# X002B.net
KiCad netlist of a schematic drawn in EAGLE
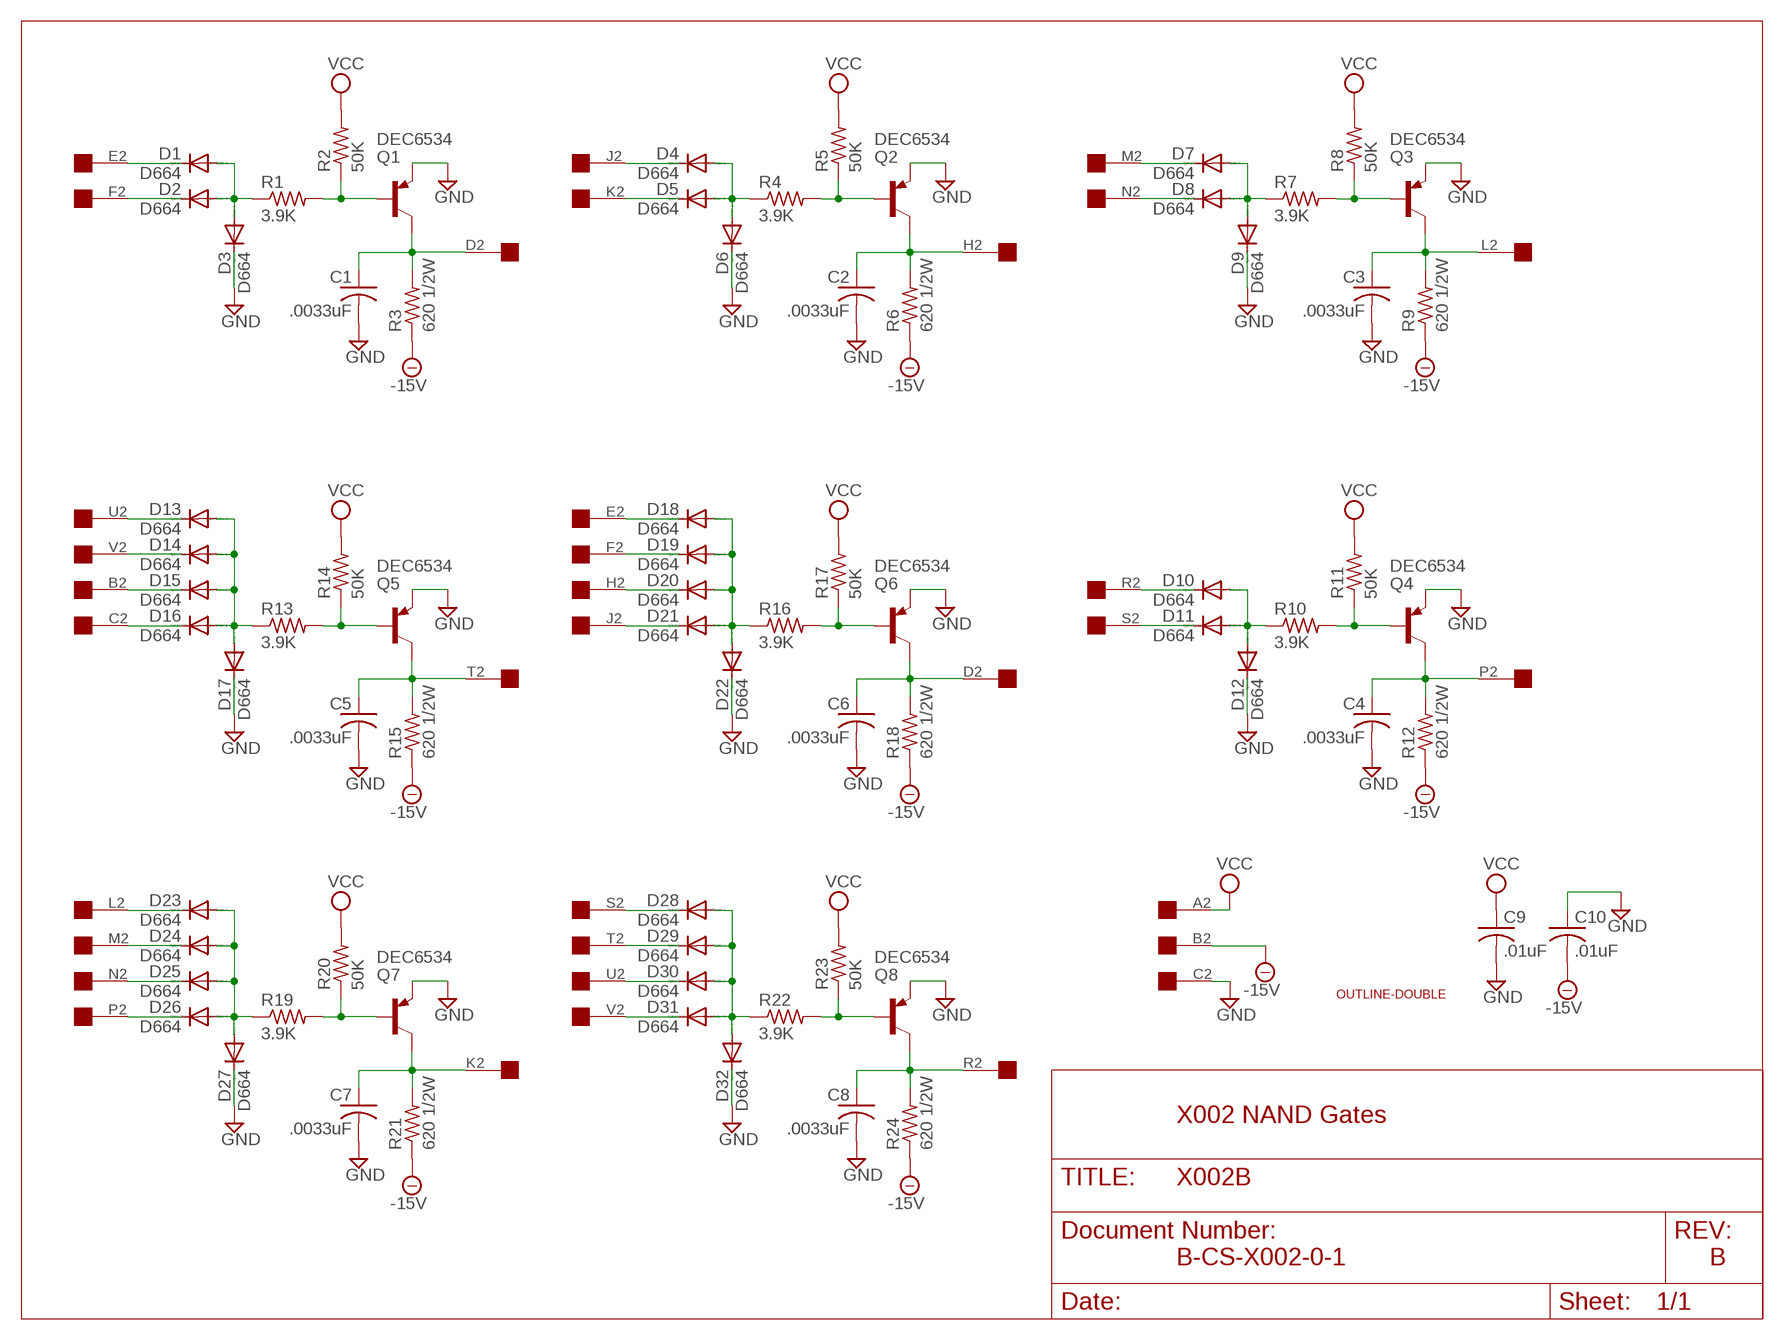
[diagram p0: schematic, sheet 1]

(export (version "E")
  (design (tool "Eeschema 10.0.6"))
  (components
    (comp (ref "A")
      (value "EDGE-1")
      (footprint "eagle-import:EDGE-CON1")
      (libsource (lib "eagle-import") (part "EDGE-1"))
    )
    (comp (ref "B")
      (value "EDGE-1")
      (footprint "eagle-import:EDGE-CON1")
      (libsource (lib "eagle-import") (part "EDGE-1"))
    )
    (comp (ref "C1")
      (value ".0033uF")
      (footprint "eagle-import:C225-062X268")
      (libsource (lib "eagle-import") (part "C-US225-062X268"))
    )
    (comp (ref "C2")
      (value ".0033uF")
      (footprint "eagle-import:C225-062X268")
      (libsource (lib "eagle-import") (part "C-US225-062X268"))
    )
    (comp (ref "C3")
      (value ".0033uF")
      (footprint "eagle-import:C225-062X268")
      (libsource (lib "eagle-import") (part "C-US225-062X268"))
    )
    (comp (ref "C4")
      (value ".0033uF")
      (footprint "eagle-import:C225-062X268")
      (libsource (lib "eagle-import") (part "C-US225-062X268"))
    )
    (comp (ref "C5")
      (value ".0033uF")
      (footprint "eagle-import:C225-062X268")
      (libsource (lib "eagle-import") (part "C-US225-062X268"))
    )
    (comp (ref "C6")
      (value ".0033uF")
      (footprint "eagle-import:C225-062X268")
      (libsource (lib "eagle-import") (part "C-US225-062X268"))
    )
    (comp (ref "C7")
      (value ".0033uF")
      (footprint "eagle-import:C225-062X268")
      (libsource (lib "eagle-import") (part "C-US225-062X268"))
    )
    (comp (ref "C8")
      (value ".0033uF")
      (footprint "eagle-import:C225-062X268")
      (libsource (lib "eagle-import") (part "C-US225-062X268"))
    )
    (comp (ref "C9")
      (value ".01uF")
      (footprint "eagle-import:C050-025X075")
      (libsource (lib "eagle-import") (part "C-US050-025X075"))
    )
    (comp (ref "C10")
      (value ".01uF")
      (footprint "eagle-import:C050-025X075")
      (libsource (lib "eagle-import") (part "C-US050-025X075"))
    )
    (comp (ref "D1")
      (value "D664")
      (footprint "eagle-import:DO35-10")
      (libsource (lib "eagle-import") (part "DIODE-DO35-10"))
    )
    (comp (ref "D2")
      (value "D664")
      (footprint "eagle-import:DO35-10")
      (libsource (lib "eagle-import") (part "DIODE-DO35-10"))
    )
    (comp (ref "D3")
      (value "D664")
      (footprint "eagle-import:DO35-10")
      (libsource (lib "eagle-import") (part "DIODE-DO35-10"))
    )
    (comp (ref "D4")
      (value "D664")
      (footprint "eagle-import:DO35-10")
      (libsource (lib "eagle-import") (part "DIODE-DO35-10"))
    )
    (comp (ref "D5")
      (value "D664")
      (footprint "eagle-import:DO35-10")
      (libsource (lib "eagle-import") (part "DIODE-DO35-10"))
    )
    (comp (ref "D6")
      (value "D664")
      (footprint "eagle-import:DO35-10")
      (libsource (lib "eagle-import") (part "DIODE-DO35-10"))
    )
    (comp (ref "D7")
      (value "D664")
      (footprint "eagle-import:DO35-10")
      (libsource (lib "eagle-import") (part "DIODE-DO35-10"))
    )
    (comp (ref "D8")
      (value "D664")
      (footprint "eagle-import:DO35-10")
      (libsource (lib "eagle-import") (part "DIODE-DO35-10"))
    )
    (comp (ref "D9")
      (value "D664")
      (footprint "eagle-import:DO35-10")
      (libsource (lib "eagle-import") (part "DIODE-DO35-10"))
    )
    (comp (ref "D10")
      (value "D664")
      (footprint "eagle-import:DO35-10")
      (libsource (lib "eagle-import") (part "DIODE-DO35-10"))
    )
    (comp (ref "D11")
      (value "D664")
      (footprint "eagle-import:DO35-10")
      (libsource (lib "eagle-import") (part "DIODE-DO35-10"))
    )
    (comp (ref "D12")
      (value "D664")
      (footprint "eagle-import:DO35-10")
      (libsource (lib "eagle-import") (part "DIODE-DO35-10"))
    )
    (comp (ref "D13")
      (value "D664")
      (footprint "eagle-import:DO35-10")
      (libsource (lib "eagle-import") (part "DIODE-DO35-10"))
    )
    (comp (ref "D14")
      (value "D664")
      (footprint "eagle-import:DO35-10")
      (libsource (lib "eagle-import") (part "DIODE-DO35-10"))
    )
    (comp (ref "D15")
      (value "D664")
      (footprint "eagle-import:DO35-10")
      (libsource (lib "eagle-import") (part "DIODE-DO35-10"))
    )
    (comp (ref "D16")
      (value "D664")
      (footprint "eagle-import:DO35-10")
      (libsource (lib "eagle-import") (part "DIODE-DO35-10"))
    )
    (comp (ref "D17")
      (value "D664")
      (footprint "eagle-import:DO35-10")
      (libsource (lib "eagle-import") (part "DIODE-DO35-10"))
    )
    (comp (ref "D18")
      (value "D664")
      (footprint "eagle-import:DO35-10")
      (libsource (lib "eagle-import") (part "DIODE-DO35-10"))
    )
    (comp (ref "D19")
      (value "D664")
      (footprint "eagle-import:DO35-10")
      (libsource (lib "eagle-import") (part "DIODE-DO35-10"))
    )
    (comp (ref "D20")
      (value "D664")
      (footprint "eagle-import:DO35-10")
      (libsource (lib "eagle-import") (part "DIODE-DO35-10"))
    )
    (comp (ref "D21")
      (value "D664")
      (footprint "eagle-import:DO35-10")
      (libsource (lib "eagle-import") (part "DIODE-DO35-10"))
    )
    (comp (ref "D22")
      (value "D664")
      (footprint "eagle-import:DO35-10")
      (libsource (lib "eagle-import") (part "DIODE-DO35-10"))
    )
    (comp (ref "D23")
      (value "D664")
      (footprint "eagle-import:DO35-10")
      (libsource (lib "eagle-import") (part "DIODE-DO35-10"))
    )
    (comp (ref "D24")
      (value "D664")
      (footprint "eagle-import:DO35-10")
      (libsource (lib "eagle-import") (part "DIODE-DO35-10"))
    )
    (comp (ref "D25")
      (value "D664")
      (footprint "eagle-import:DO35-10")
      (libsource (lib "eagle-import") (part "DIODE-DO35-10"))
    )
    (comp (ref "D26")
      (value "D664")
      (footprint "eagle-import:DO35-10")
      (libsource (lib "eagle-import") (part "DIODE-DO35-10"))
    )
    (comp (ref "D27")
      (value "D664")
      (footprint "eagle-import:DO35-10")
      (libsource (lib "eagle-import") (part "DIODE-DO35-10"))
    )
    (comp (ref "D28")
      (value "D664")
      (footprint "eagle-import:DO35-10")
      (libsource (lib "eagle-import") (part "DIODE-DO35-10"))
    )
    (comp (ref "D29")
      (value "D664")
      (footprint "eagle-import:DO35-10")
      (libsource (lib "eagle-import") (part "DIODE-DO35-10"))
    )
    (comp (ref "D30")
      (value "D664")
      (footprint "eagle-import:DO35-10")
      (libsource (lib "eagle-import") (part "DIODE-DO35-10"))
    )
    (comp (ref "D31")
      (value "D664")
      (footprint "eagle-import:DO35-10")
      (libsource (lib "eagle-import") (part "DIODE-DO35-10"))
    )
    (comp (ref "D32")
      (value "D664")
      (footprint "eagle-import:DO35-10")
      (libsource (lib "eagle-import") (part "DIODE-DO35-10"))
    )
    (comp (ref "Q1")
      (value "DEC6534")
      (footprint "eagle-import:TO5")
      (libsource (lib "eagle-import") (part "-PNP-TO5"))
    )
    (comp (ref "Q2")
      (value "DEC6534")
      (footprint "eagle-import:TO5")
      (libsource (lib "eagle-import") (part "-PNP-TO5"))
    )
    (comp (ref "Q3")
      (value "DEC6534")
      (footprint "eagle-import:TO5")
      (libsource (lib "eagle-import") (part "-PNP-TO5"))
    )
    (comp (ref "Q4")
      (value "DEC6534")
      (footprint "eagle-import:TO5")
      (libsource (lib "eagle-import") (part "-PNP-TO5"))
    )
    (comp (ref "Q5")
      (value "DEC6534")
      (footprint "eagle-import:TO5")
      (libsource (lib "eagle-import") (part "-PNP-TO5"))
    )
    (comp (ref "Q6")
      (value "DEC6534")
      (footprint "eagle-import:TO5")
      (libsource (lib "eagle-import") (part "-PNP-TO5"))
    )
    (comp (ref "Q7")
      (value "DEC6534")
      (footprint "eagle-import:TO5")
      (libsource (lib "eagle-import") (part "-PNP-TO5"))
    )
    (comp (ref "Q8")
      (value "DEC6534")
      (footprint "eagle-import:TO5")
      (libsource (lib "eagle-import") (part "-PNP-TO5"))
    )
    (comp (ref "R1")
      (value "3.9K")
      (footprint "eagle-import:0207_10")
      (libsource (lib "eagle-import") (part "R-US_0207/10"))
    )
    (comp (ref "R2")
      (value "50K")
      (footprint "eagle-import:0207_10")
      (libsource (lib "eagle-import") (part "R-US_0207/10"))
    )
    (comp (ref "R3")
      (value "620 1/2W")
      (footprint "eagle-import:0414_15")
      (libsource (lib "eagle-import") (part "R-US_0414/15"))
    )
    (comp (ref "R4")
      (value "3.9K")
      (footprint "eagle-import:0207_10")
      (libsource (lib "eagle-import") (part "R-US_0207/10"))
    )
    (comp (ref "R5")
      (value "50K")
      (footprint "eagle-import:0207_10")
      (libsource (lib "eagle-import") (part "R-US_0207/10"))
    )
    (comp (ref "R6")
      (value "620 1/2W")
      (footprint "eagle-import:0414_15")
      (libsource (lib "eagle-import") (part "R-US_0414/15"))
    )
    (comp (ref "R7")
      (value "3.9K")
      (footprint "eagle-import:0207_10")
      (libsource (lib "eagle-import") (part "R-US_0207/10"))
    )
    (comp (ref "R8")
      (value "50K")
      (footprint "eagle-import:0207_10")
      (libsource (lib "eagle-import") (part "R-US_0207/10"))
    )
    (comp (ref "R9")
      (value "620 1/2W")
      (footprint "eagle-import:0414_15")
      (libsource (lib "eagle-import") (part "R-US_0414/15"))
    )
    (comp (ref "R10")
      (value "3.9K")
      (footprint "eagle-import:0207_10")
      (libsource (lib "eagle-import") (part "R-US_0207/10"))
    )
    (comp (ref "R11")
      (value "50K")
      (footprint "eagle-import:0207_10")
      (libsource (lib "eagle-import") (part "R-US_0207/10"))
    )
    (comp (ref "R12")
      (value "620 1/2W")
      (footprint "eagle-import:0414_15")
      (libsource (lib "eagle-import") (part "R-US_0414/15"))
    )
    (comp (ref "R13")
      (value "3.9K")
      (footprint "eagle-import:0207_10")
      (libsource (lib "eagle-import") (part "R-US_0207/10"))
    )
    (comp (ref "R14")
      (value "50K")
      (footprint "eagle-import:0207_10")
      (libsource (lib "eagle-import") (part "R-US_0207/10"))
    )
    (comp (ref "R15")
      (value "620 1/2W")
      (footprint "eagle-import:0414_15")
      (libsource (lib "eagle-import") (part "R-US_0414/15"))
    )
    (comp (ref "R16")
      (value "3.9K")
      (footprint "eagle-import:0207_10")
      (libsource (lib "eagle-import") (part "R-US_0207/10"))
    )
    (comp (ref "R17")
      (value "50K")
      (footprint "eagle-import:0207_10")
      (libsource (lib "eagle-import") (part "R-US_0207/10"))
    )
    (comp (ref "R18")
      (value "620 1/2W")
      (footprint "eagle-import:0414_15")
      (libsource (lib "eagle-import") (part "R-US_0414/15"))
    )
    (comp (ref "R19")
      (value "3.9K")
      (footprint "eagle-import:0207_10")
      (libsource (lib "eagle-import") (part "R-US_0207/10"))
    )
    (comp (ref "R20")
      (value "50K")
      (footprint "eagle-import:0207_10")
      (libsource (lib "eagle-import") (part "R-US_0207/10"))
    )
    (comp (ref "R21")
      (value "620 1/2W")
      (footprint "eagle-import:0414_15")
      (libsource (lib "eagle-import") (part "R-US_0414/15"))
    )
    (comp (ref "R22")
      (value "3.9K")
      (footprint "eagle-import:0207_10")
      (libsource (lib "eagle-import") (part "R-US_0207/10"))
    )
    (comp (ref "R23")
      (value "50K")
      (footprint "eagle-import:0207_10")
      (libsource (lib "eagle-import") (part "R-US_0207/10"))
    )
    (comp (ref "R24")
      (value "620 1/2W")
      (footprint "eagle-import:0414_15")
      (libsource (lib "eagle-import") (part "R-US_0414/15"))
    )
    (comp (ref "U$1")
      (value "OUTLINE-DOUBLE")
      (footprint "eagle-import:DOUBLE")
      (libsource (lib "eagle-import") (part "OUTLINE-DOUBLE"))
    )
  )
  (nets
    (net (code "1") (name "-15V") (class "Default")
      (node (ref "A") (pin "B2") (pinfunction "1_B2") (pintype "bidirectional"))
      (node (ref "C10") (pin "2") (pinfunction "2_2") (pintype "passive"))
      (node (ref "R12") (pin "1") (pinfunction "1_1") (pintype "passive"))
      (node (ref "R15") (pin "1") (pinfunction "1_1") (pintype "passive"))
      (node (ref "R18") (pin "1") (pinfunction "1_1") (pintype "passive"))
      (node (ref "R21") (pin "1") (pinfunction "1_1") (pintype "passive"))
      (node (ref "R24") (pin "1") (pinfunction "1_1") (pintype "passive"))
      (node (ref "R3") (pin "1") (pinfunction "1_1") (pintype "passive"))
      (node (ref "R6") (pin "1") (pinfunction "1_1") (pintype "passive"))
      (node (ref "R9") (pin "1") (pinfunction "1_1") (pintype "passive"))
    )
    (net (code "2") (name "GND") (class "Default")
      (node (ref "A") (pin "C2") (pinfunction "1_C2") (pintype "bidirectional"))
      (node (ref "C1") (pin "2") (pinfunction "2_2") (pintype "passive"))
      (node (ref "C10") (pin "1") (pinfunction "1_1") (pintype "passive"))
      (node (ref "C2") (pin "2") (pinfunction "2_2") (pintype "passive"))
      (node (ref "C3") (pin "2") (pinfunction "2_2") (pintype "passive"))
      (node (ref "C4") (pin "2") (pinfunction "2_2") (pintype "passive"))
      (node (ref "C5") (pin "2") (pinfunction "2_2") (pintype "passive"))
      (node (ref "C6") (pin "2") (pinfunction "2_2") (pintype "passive"))
      (node (ref "C7") (pin "2") (pinfunction "2_2") (pintype "passive"))
      (node (ref "C8") (pin "2") (pinfunction "2_2") (pintype "passive"))
      (node (ref "C9") (pin "2") (pinfunction "2_2") (pintype "passive"))
      (node (ref "D12") (pin "C") (pinfunction "C_C") (pintype "passive"))
      (node (ref "D17") (pin "C") (pinfunction "C_C") (pintype "passive"))
      (node (ref "D22") (pin "C") (pinfunction "C_C") (pintype "passive"))
      (node (ref "D27") (pin "C") (pinfunction "C_C") (pintype "passive"))
      (node (ref "D3") (pin "C") (pinfunction "C_C") (pintype "passive"))
      (node (ref "D32") (pin "C") (pinfunction "C_C") (pintype "passive"))
      (node (ref "D6") (pin "C") (pinfunction "C_C") (pintype "passive"))
      (node (ref "D9") (pin "C") (pinfunction "C_C") (pintype "passive"))
      (node (ref "Q1") (pin "1") (pinfunction "E_1") (pintype "passive"))
      (node (ref "Q2") (pin "1") (pinfunction "E_1") (pintype "passive"))
      (node (ref "Q3") (pin "1") (pinfunction "E_1") (pintype "passive"))
      (node (ref "Q4") (pin "1") (pinfunction "E_1") (pintype "passive"))
      (node (ref "Q5") (pin "1") (pinfunction "E_1") (pintype "passive"))
      (node (ref "Q6") (pin "1") (pinfunction "E_1") (pintype "passive"))
      (node (ref "Q7") (pin "1") (pinfunction "E_1") (pintype "passive"))
      (node (ref "Q8") (pin "1") (pinfunction "E_1") (pintype "passive"))
    )
    (net (code "3") (name "Net-(AD-1)") (class "Default")
      (node (ref "A") (pin "D2") (pinfunction "1_D2") (pintype "bidirectional"))
      (node (ref "C1") (pin "1") (pinfunction "1_1") (pintype "passive"))
      (node (ref "Q1") (pin "3") (pinfunction "C_3") (pintype "passive"))
      (node (ref "R3") (pin "2") (pinfunction "2_2") (pintype "passive"))
    )
    (net (code "4") (name "Net-(AE-1)") (class "Default")
      (node (ref "A") (pin "E2") (pinfunction "1_E2") (pintype "bidirectional"))
      (node (ref "D1") (pin "C") (pinfunction "C_C") (pintype "passive"))
    )
    (net (code "5") (name "Net-(AF-1)") (class "Default")
      (node (ref "A") (pin "F2") (pinfunction "1_F2") (pintype "bidirectional"))
      (node (ref "D2") (pin "C") (pinfunction "C_C") (pintype "passive"))
    )
    (net (code "6") (name "Net-(AG-1)") (class "Default")
      (node (ref "A") (pin "H2") (pinfunction "1_H2") (pintype "bidirectional"))
      (node (ref "C2") (pin "1") (pinfunction "1_1") (pintype "passive"))
      (node (ref "Q2") (pin "3") (pinfunction "C_3") (pintype "passive"))
      (node (ref "R6") (pin "2") (pinfunction "2_2") (pintype "passive"))
    )
    (net (code "7") (name "Net-(AH-1)") (class "Default")
      (node (ref "A") (pin "J2") (pinfunction "1_J2") (pintype "bidirectional"))
      (node (ref "D4") (pin "C") (pinfunction "C_C") (pintype "passive"))
    )
    (net (code "8") (name "Net-(AI-1)") (class "Default")
      (node (ref "A") (pin "K2") (pinfunction "1_K2") (pintype "bidirectional"))
      (node (ref "D5") (pin "C") (pinfunction "C_C") (pintype "passive"))
    )
    (net (code "9") (name "Net-(AJ-1)") (class "Default")
      (node (ref "A") (pin "L2") (pinfunction "1_L2") (pintype "bidirectional"))
      (node (ref "C3") (pin "1") (pinfunction "1_1") (pintype "passive"))
      (node (ref "Q3") (pin "3") (pinfunction "C_3") (pintype "passive"))
      (node (ref "R9") (pin "2") (pinfunction "2_2") (pintype "passive"))
    )
    (net (code "10") (name "Net-(AK-1)") (class "Default")
      (node (ref "A") (pin "M2") (pinfunction "1_M2") (pintype "bidirectional"))
      (node (ref "D7") (pin "C") (pinfunction "C_C") (pintype "passive"))
    )
    (net (code "11") (name "Net-(AL-1)") (class "Default")
      (node (ref "A") (pin "N2") (pinfunction "1_N2") (pintype "bidirectional"))
      (node (ref "D8") (pin "C") (pinfunction "C_C") (pintype "passive"))
    )
    (net (code "12") (name "Net-(AM-1)") (class "Default")
      (node (ref "A") (pin "P2") (pinfunction "1_P2") (pintype "bidirectional"))
      (node (ref "C4") (pin "1") (pinfunction "1_1") (pintype "passive"))
      (node (ref "Q4") (pin "3") (pinfunction "C_3") (pintype "passive"))
      (node (ref "R12") (pin "2") (pinfunction "2_2") (pintype "passive"))
    )
    (net (code "13") (name "Net-(AN-1)") (class "Default")
      (node (ref "A") (pin "R2") (pinfunction "1_R2") (pintype "bidirectional"))
      (node (ref "D10") (pin "C") (pinfunction "C_C") (pintype "passive"))
    )
    (net (code "14") (name "Net-(AO-1)") (class "Default")
      (node (ref "A") (pin "S2") (pinfunction "1_S2") (pintype "bidirectional"))
      (node (ref "D11") (pin "C") (pinfunction "C_C") (pintype "passive"))
    )
    (net (code "15") (name "Net-(AP-1)") (class "Default")
      (node (ref "A") (pin "T2") (pinfunction "1_T2") (pintype "bidirectional"))
      (node (ref "C5") (pin "1") (pinfunction "1_1") (pintype "passive"))
      (node (ref "Q5") (pin "3") (pinfunction "C_3") (pintype "passive"))
      (node (ref "R15") (pin "2") (pinfunction "2_2") (pintype "passive"))
    )
    (net (code "16") (name "Net-(AQ-1)") (class "Default")
      (node (ref "A") (pin "U2") (pinfunction "1_U2") (pintype "bidirectional"))
      (node (ref "D13") (pin "C") (pinfunction "C_C") (pintype "passive"))
    )
    (net (code "17") (name "Net-(AR-1)") (class "Default")
      (node (ref "A") (pin "V2") (pinfunction "1_V2") (pintype "bidirectional"))
      (node (ref "D14") (pin "C") (pinfunction "C_C") (pintype "passive"))
    )
    (net (code "18") (name "Net-(BB-1)") (class "Default")
      (node (ref "B") (pin "B2") (pinfunction "1_B2") (pintype "bidirectional"))
      (node (ref "D15") (pin "C") (pinfunction "C_C") (pintype "passive"))
    )
    (net (code "19") (name "Net-(BC-1)") (class "Default")
      (node (ref "B") (pin "C2") (pinfunction "1_C2") (pintype "bidirectional"))
      (node (ref "D16") (pin "C") (pinfunction "C_C") (pintype "passive"))
    )
    (net (code "20") (name "Net-(BD-1)") (class "Default")
      (node (ref "B") (pin "D2") (pinfunction "1_D2") (pintype "bidirectional"))
      (node (ref "C6") (pin "1") (pinfunction "1_1") (pintype "passive"))
      (node (ref "Q6") (pin "3") (pinfunction "C_3") (pintype "passive"))
      (node (ref "R18") (pin "2") (pinfunction "2_2") (pintype "passive"))
    )
    (net (code "21") (name "Net-(BE-1)") (class "Default")
      (node (ref "B") (pin "E2") (pinfunction "1_E2") (pintype "bidirectional"))
      (node (ref "D18") (pin "C") (pinfunction "C_C") (pintype "passive"))
    )
    (net (code "22") (name "Net-(BF-1)") (class "Default")
      (node (ref "B") (pin "F2") (pinfunction "1_F2") (pintype "bidirectional"))
      (node (ref "D19") (pin "C") (pinfunction "C_C") (pintype "passive"))
    )
    (net (code "23") (name "Net-(BG-1)") (class "Default")
      (node (ref "B") (pin "H2") (pinfunction "1_H2") (pintype "bidirectional"))
      (node (ref "D20") (pin "C") (pinfunction "C_C") (pintype "passive"))
    )
    (net (code "24") (name "Net-(BH-1)") (class "Default")
      (node (ref "B") (pin "J2") (pinfunction "1_J2") (pintype "bidirectional"))
      (node (ref "D21") (pin "C") (pinfunction "C_C") (pintype "passive"))
    )
    (net (code "25") (name "Net-(BI-1)") (class "Default")
      (node (ref "B") (pin "K2") (pinfunction "1_K2") (pintype "bidirectional"))
      (node (ref "C7") (pin "1") (pinfunction "1_1") (pintype "passive"))
      (node (ref "Q7") (pin "3") (pinfunction "C_3") (pintype "passive"))
      (node (ref "R21") (pin "2") (pinfunction "2_2") (pintype "passive"))
    )
    (net (code "26") (name "Net-(BJ-1)") (class "Default")
      (node (ref "B") (pin "L2") (pinfunction "1_L2") (pintype "bidirectional"))
      (node (ref "D23") (pin "C") (pinfunction "C_C") (pintype "passive"))
    )
    (net (code "27") (name "Net-(BK-1)") (class "Default")
      (node (ref "B") (pin "M2") (pinfunction "1_M2") (pintype "bidirectional"))
      (node (ref "D24") (pin "C") (pinfunction "C_C") (pintype "passive"))
    )
    (net (code "28") (name "Net-(BL-1)") (class "Default")
      (node (ref "B") (pin "N2") (pinfunction "1_N2") (pintype "bidirectional"))
      (node (ref "D25") (pin "C") (pinfunction "C_C") (pintype "passive"))
    )
    (net (code "29") (name "Net-(BM-1)") (class "Default")
      (node (ref "B") (pin "P2") (pinfunction "1_P2") (pintype "bidirectional"))
      (node (ref "D26") (pin "C") (pinfunction "C_C") (pintype "passive"))
    )
    (net (code "30") (name "Net-(BN-1)") (class "Default")
      (node (ref "B") (pin "R2") (pinfunction "1_R2") (pintype "bidirectional"))
      (node (ref "C8") (pin "1") (pinfunction "1_1") (pintype "passive"))
      (node (ref "Q8") (pin "3") (pinfunction "C_3") (pintype "passive"))
      (node (ref "R24") (pin "2") (pinfunction "2_2") (pintype "passive"))
    )
    (net (code "31") (name "Net-(BO-1)") (class "Default")
      (node (ref "B") (pin "S2") (pinfunction "1_S2") (pintype "bidirectional"))
      (node (ref "D28") (pin "C") (pinfunction "C_C") (pintype "passive"))
    )
    (net (code "32") (name "Net-(BP-1)") (class "Default")
      (node (ref "B") (pin "T2") (pinfunction "1_T2") (pintype "bidirectional"))
      (node (ref "D29") (pin "C") (pinfunction "C_C") (pintype "passive"))
    )
    (net (code "33") (name "Net-(BQ-1)") (class "Default")
      (node (ref "B") (pin "U2") (pinfunction "1_U2") (pintype "bidirectional"))
      (node (ref "D30") (pin "C") (pinfunction "C_C") (pintype "passive"))
    )
    (net (code "34") (name "Net-(BR-1)") (class "Default")
      (node (ref "B") (pin "V2") (pinfunction "1_V2") (pintype "bidirectional"))
      (node (ref "D31") (pin "C") (pinfunction "C_C") (pintype "passive"))
    )
    (net (code "35") (name "Net-(D1-PadA)") (class "Default")
      (node (ref "D1") (pin "A") (pinfunction "A_A") (pintype "passive"))
      (node (ref "D2") (pin "A") (pinfunction "A_A") (pintype "passive"))
      (node (ref "D3") (pin "A") (pinfunction "A_A") (pintype "passive"))
      (node (ref "R1") (pin "1") (pinfunction "1_1") (pintype "passive"))
    )
    (net (code "36") (name "Net-(D4-PadA)") (class "Default")
      (node (ref "D4") (pin "A") (pinfunction "A_A") (pintype "passive"))
      (node (ref "D5") (pin "A") (pinfunction "A_A") (pintype "passive"))
      (node (ref "D6") (pin "A") (pinfunction "A_A") (pintype "passive"))
      (node (ref "R4") (pin "1") (pinfunction "1_1") (pintype "passive"))
    )
    (net (code "37") (name "Net-(D7-PadA)") (class "Default")
      (node (ref "D7") (pin "A") (pinfunction "A_A") (pintype "passive"))
      (node (ref "D8") (pin "A") (pinfunction "A_A") (pintype "passive"))
      (node (ref "D9") (pin "A") (pinfunction "A_A") (pintype "passive"))
      (node (ref "R7") (pin "1") (pinfunction "1_1") (pintype "passive"))
    )
    (net (code "38") (name "Net-(D10-PadA)") (class "Default")
      (node (ref "D10") (pin "A") (pinfunction "A_A") (pintype "passive"))
      (node (ref "D11") (pin "A") (pinfunction "A_A") (pintype "passive"))
      (node (ref "D12") (pin "A") (pinfunction "A_A") (pintype "passive"))
      (node (ref "R10") (pin "1") (pinfunction "1_1") (pintype "passive"))
    )
    (net (code "39") (name "Net-(D13-PadA)") (class "Default")
      (node (ref "D13") (pin "A") (pinfunction "A_A") (pintype "passive"))
      (node (ref "D14") (pin "A") (pinfunction "A_A") (pintype "passive"))
      (node (ref "D15") (pin "A") (pinfunction "A_A") (pintype "passive"))
      (node (ref "D16") (pin "A") (pinfunction "A_A") (pintype "passive"))
      (node (ref "D17") (pin "A") (pinfunction "A_A") (pintype "passive"))
      (node (ref "R13") (pin "1") (pinfunction "1_1") (pintype "passive"))
    )
    (net (code "40") (name "Net-(D18-PadA)") (class "Default")
      (node (ref "D18") (pin "A") (pinfunction "A_A") (pintype "passive"))
      (node (ref "D19") (pin "A") (pinfunction "A_A") (pintype "passive"))
      (node (ref "D20") (pin "A") (pinfunction "A_A") (pintype "passive"))
      (node (ref "D21") (pin "A") (pinfunction "A_A") (pintype "passive"))
      (node (ref "D22") (pin "A") (pinfunction "A_A") (pintype "passive"))
      (node (ref "R16") (pin "1") (pinfunction "1_1") (pintype "passive"))
    )
    (net (code "41") (name "Net-(D23-PadA)") (class "Default")
      (node (ref "D23") (pin "A") (pinfunction "A_A") (pintype "passive"))
      (node (ref "D24") (pin "A") (pinfunction "A_A") (pintype "passive"))
      (node (ref "D25") (pin "A") (pinfunction "A_A") (pintype "passive"))
      (node (ref "D26") (pin "A") (pinfunction "A_A") (pintype "passive"))
      (node (ref "D27") (pin "A") (pinfunction "A_A") (pintype "passive"))
      (node (ref "R19") (pin "1") (pinfunction "1_1") (pintype "passive"))
    )
    (net (code "42") (name "Net-(D28-PadA)") (class "Default")
      (node (ref "D28") (pin "A") (pinfunction "A_A") (pintype "passive"))
      (node (ref "D29") (pin "A") (pinfunction "A_A") (pintype "passive"))
      (node (ref "D30") (pin "A") (pinfunction "A_A") (pintype "passive"))
      (node (ref "D31") (pin "A") (pinfunction "A_A") (pintype "passive"))
      (node (ref "D32") (pin "A") (pinfunction "A_A") (pintype "passive"))
      (node (ref "R22") (pin "1") (pinfunction "1_1") (pintype "passive"))
    )
    (net (code "43") (name "Net-(Q1-B)") (class "Default")
      (node (ref "Q1") (pin "2") (pinfunction "B_2") (pintype "passive"))
      (node (ref "R1") (pin "2") (pinfunction "2_2") (pintype "passive"))
      (node (ref "R2") (pin "1") (pinfunction "1_1") (pintype "passive"))
    )
    (net (code "44") (name "Net-(Q2-B)") (class "Default")
      (node (ref "Q2") (pin "2") (pinfunction "B_2") (pintype "passive"))
      (node (ref "R4") (pin "2") (pinfunction "2_2") (pintype "passive"))
      (node (ref "R5") (pin "1") (pinfunction "1_1") (pintype "passive"))
    )
    (net (code "45") (name "Net-(Q3-B)") (class "Default")
      (node (ref "Q3") (pin "2") (pinfunction "B_2") (pintype "passive"))
      (node (ref "R7") (pin "2") (pinfunction "2_2") (pintype "passive"))
      (node (ref "R8") (pin "1") (pinfunction "1_1") (pintype "passive"))
    )
    (net (code "46") (name "Net-(Q4-B)") (class "Default")
      (node (ref "Q4") (pin "2") (pinfunction "B_2") (pintype "passive"))
      (node (ref "R10") (pin "2") (pinfunction "2_2") (pintype "passive"))
      (node (ref "R11") (pin "1") (pinfunction "1_1") (pintype "passive"))
    )
    (net (code "47") (name "Net-(Q5-B)") (class "Default")
      (node (ref "Q5") (pin "2") (pinfunction "B_2") (pintype "passive"))
      (node (ref "R13") (pin "2") (pinfunction "2_2") (pintype "passive"))
      (node (ref "R14") (pin "1") (pinfunction "1_1") (pintype "passive"))
    )
    (net (code "48") (name "Net-(Q6-B)") (class "Default")
      (node (ref "Q6") (pin "2") (pinfunction "B_2") (pintype "passive"))
      (node (ref "R16") (pin "2") (pinfunction "2_2") (pintype "passive"))
      (node (ref "R17") (pin "1") (pinfunction "1_1") (pintype "passive"))
    )
    (net (code "49") (name "Net-(Q7-B)") (class "Default")
      (node (ref "Q7") (pin "2") (pinfunction "B_2") (pintype "passive"))
      (node (ref "R19") (pin "2") (pinfunction "2_2") (pintype "passive"))
      (node (ref "R20") (pin "1") (pinfunction "1_1") (pintype "passive"))
    )
    (net (code "50") (name "Net-(Q8-B)") (class "Default")
      (node (ref "Q8") (pin "2") (pinfunction "B_2") (pintype "passive"))
      (node (ref "R22") (pin "2") (pinfunction "2_2") (pintype "passive"))
      (node (ref "R23") (pin "1") (pinfunction "1_1") (pintype "passive"))
    )
    (net (code "51") (name "VCC") (class "Default")
      (node (ref "A") (pin "A2") (pinfunction "1_A2") (pintype "bidirectional"))
      (node (ref "C9") (pin "1") (pinfunction "1_1") (pintype "passive"))
      (node (ref "R11") (pin "2") (pinfunction "2_2") (pintype "passive"))
      (node (ref "R14") (pin "2") (pinfunction "2_2") (pintype "passive"))
      (node (ref "R17") (pin "2") (pinfunction "2_2") (pintype "passive"))
      (node (ref "R2") (pin "2") (pinfunction "2_2") (pintype "passive"))
      (node (ref "R20") (pin "2") (pinfunction "2_2") (pintype "passive"))
      (node (ref "R23") (pin "2") (pinfunction "2_2") (pintype "passive"))
      (node (ref "R5") (pin "2") (pinfunction "2_2") (pintype "passive"))
      (node (ref "R8") (pin "2") (pinfunction "2_2") (pintype "passive"))
    )
  )
)
